# PowerMinder1sch.net
KiCad netlist of a schematic drawn in EAGLE
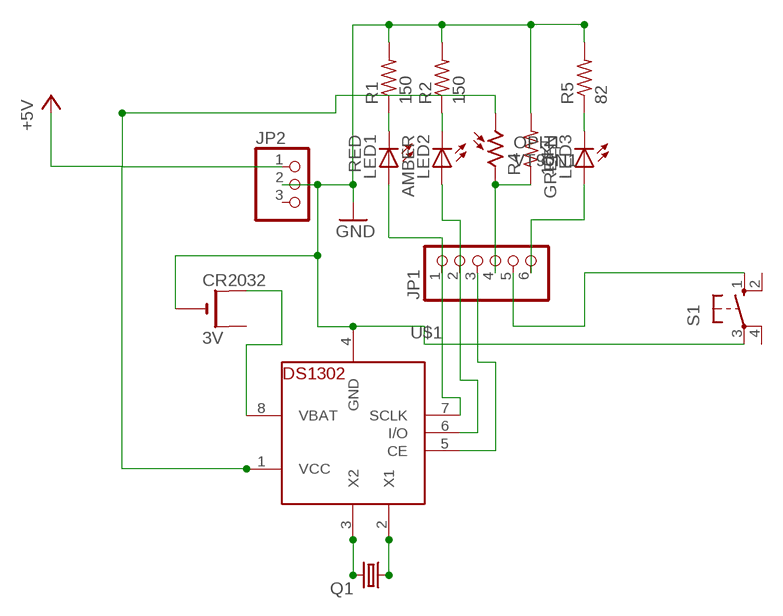
[diagram p0: schematic, sheet 1]

(export (version "E")
  (design (tool "Eeschema 10.0.6"))
  (components
    (comp (ref "CR2032")
      (value "3V")
      (footprint "eagle-import:CR2032-THRU")
      (libsource (lib "eagle-import") (part "CR2032THM"))
    )
    (comp (ref "JP1")
      (value "PINHD-1X6")
      (footprint "eagle-import:1X06")
      (libsource (lib "eagle-import") (part "PINHD-1X6"))
    )
    (comp (ref "JP2")
      (value "PINHD-1X3")
      (footprint "eagle-import:1X03")
      (libsource (lib "eagle-import") (part "PINHD-1X3"))
    )
    (comp (ref "LED1")
      (value "RED")
      (footprint "eagle-import:LED5MM")
      (libsource (lib "eagle-import") (part "LED5MM"))
    )
    (comp (ref "LED2")
      (value "AMBER")
      (footprint "eagle-import:LED5MM")
      (libsource (lib "eagle-import") (part "LED5MM"))
    )
    (comp (ref "LED3")
      (value "GREEN")
      (footprint "eagle-import:LED5MM")
      (libsource (lib "eagle-import") (part "LED5MM"))
    )
    (comp (ref "OPH1")
      (value "VT90N1")
      (footprint "eagle-import:VT900")
      (libsource (lib "eagle-import") (part "VT90N1"))
    )
    (comp (ref "Q1")
      (value "CRYSTALTC26H")
      (footprint "eagle-import:TC26H")
      (libsource (lib "eagle-import") (part "CRYSTALTC26H"))
    )
    (comp (ref "R1")
      (value "150")
      (footprint "eagle-import:0207_12")
      (libsource (lib "eagle-import") (part "R-US_0207/12"))
    )
    (comp (ref "R2")
      (value "150")
      (footprint "eagle-import:0207_12")
      (libsource (lib "eagle-import") (part "R-US_0207/12"))
    )
    (comp (ref "R4")
      (value "10K")
      (footprint "eagle-import:0207_12")
      (libsource (lib "eagle-import") (part "R-US_0207/12"))
    )
    (comp (ref "R5")
      (value "82")
      (footprint "eagle-import:0207_12")
      (libsource (lib "eagle-import") (part "R-US_0207/12"))
    )
    (comp (ref "S1")
      (value "10-XX")
      (footprint "eagle-import:B3F-10XX")
      (fields (field (name "MPN") "B3F-1000"))
      (libsource (lib "eagle-import") (part "10-XX"))
    )
    (comp (ref "U$1")
      (value "DS1302")
      (footprint "eagle-import:DIL08-ROUND")
      (libsource (lib "eagle-import") (part "DS1302"))
    )
  )
  (nets
    (net (code "1") (name "+5V") (class "Default")
      (node (ref "JP2") (pin "1") (pinfunction "1_1") (pintype "passive"))
      (node (ref "OPH1") (pin "1") (pinfunction "1_1") (pintype "passive"))
      (node (ref "U$1") (pin "1") (pinfunction "VCC_1") (pintype "power_in"))
    )
    (net (code "2") (name "GND") (class "Default")
      (node (ref "CR2032") (pin "-") (pinfunction "-_-") (pintype "passive"))
      (node (ref "JP2") (pin "2") (pinfunction "2_2") (pintype "passive"))
      (node (ref "R1") (pin "2") (pinfunction "2_2") (pintype "passive"))
      (node (ref "R2") (pin "2") (pinfunction "2_2") (pintype "passive"))
      (node (ref "R4") (pin "2") (pinfunction "2_2") (pintype "passive"))
      (node (ref "R5") (pin "2") (pinfunction "2_2") (pintype "passive"))
      (node (ref "S1") (pin "3") (pinfunction "P_3") (pintype "passive"))
      (node (ref "U$1") (pin "4") (pinfunction "GND_4") (pintype "power_in"))
    )
    (net (code "3") (name "Net-(CR2032-+)") (class "Default")
      (node (ref "CR2032") (pin "+1") (pinfunction "+_+1") (pintype "passive"))
      (node (ref "U$1") (pin "8") (pinfunction "VBAT_8") (pintype "power_in"))
    )
    (net (code "4") (name "Net-(JP1-Pad4)") (class "Default")
      (node (ref "JP1") (pin "4") (pinfunction "4_4") (pintype "passive"))
      (node (ref "OPH1") (pin "2") (pinfunction "2_2") (pintype "passive"))
      (node (ref "R4") (pin "1") (pinfunction "1_1") (pintype "passive"))
    )
    (net (code "5") (name "Net-(JP1-Pad6)") (class "Default")
      (node (ref "JP1") (pin "6") (pinfunction "6_6") (pintype "passive"))
      (node (ref "LED3") (pin "A") (pinfunction "A_A") (pintype "passive"))
    )
    (net (code "6") (name "Net-(LED1-C)") (class "Default")
      (node (ref "LED1") (pin "K") (pinfunction "C_K") (pintype "passive"))
      (node (ref "R1") (pin "1") (pinfunction "1_1") (pintype "passive"))
    )
    (net (code "7") (name "Net-(LED2-C)") (class "Default")
      (node (ref "LED2") (pin "K") (pinfunction "C_K") (pintype "passive"))
      (node (ref "R2") (pin "1") (pinfunction "1_1") (pintype "passive"))
    )
    (net (code "8") (name "Net-(LED3-C)") (class "Default")
      (node (ref "LED3") (pin "K") (pinfunction "C_K") (pintype "passive"))
      (node (ref "R5") (pin "1") (pinfunction "1_1") (pintype "passive"))
    )
    (net (code "9") (name "Net-(S1-S)") (class "Default")
      (node (ref "JP1") (pin "5") (pinfunction "5_5") (pintype "passive"))
      (node (ref "S1") (pin "1") (pinfunction "S_1") (pintype "passive"))
    )
    (net (code "10") (name "Net-(U$1-CE)") (class "Default")
      (node (ref "JP1") (pin "3") (pinfunction "3_3") (pintype "passive"))
      (node (ref "U$1") (pin "5") (pinfunction "CE_5") (pintype "input"))
    )
    (net (code "11") (name "Net-(U$1-I{slash}O)") (class "Default")
      (node (ref "JP1") (pin "2") (pinfunction "2_2") (pintype "passive"))
      (node (ref "LED2") (pin "A") (pinfunction "A_A") (pintype "passive"))
      (node (ref "U$1") (pin "6") (pinfunction "I/O_6") (pintype "bidirectional"))
    )
    (net (code "12") (name "Net-(U$1-SCLK)") (class "Default")
      (node (ref "JP1") (pin "1") (pinfunction "1_1") (pintype "passive"))
      (node (ref "LED1") (pin "A") (pinfunction "A_A") (pintype "passive"))
      (node (ref "U$1") (pin "7") (pinfunction "SCLK_7") (pintype "input"))
    )
    (net (code "13") (name "Net-(U$1-X1)") (class "Default")
      (node (ref "Q1") (pin "1") (pinfunction "1_1") (pintype "passive"))
      (node (ref "U$1") (pin "2") (pinfunction "X1_2") (pintype "passive"))
    )
    (net (code "14") (name "Net-(U$1-X2)") (class "Default")
      (node (ref "Q1") (pin "2") (pinfunction "2_2") (pintype "passive"))
      (node (ref "U$1") (pin "3") (pinfunction "X2_3") (pintype "passive"))
    )
    (net (code "15") (name "unconnected-(CR2032-+1-Pad+2)") (class "Default")
      (node (ref "CR2032") (pin "+2") (pinfunction "+1_+2") (pintype "passive"))
    )
    (net (code "16") (name "unconnected-(JP2-Pad3)") (class "Default")
      (node (ref "JP2") (pin "3") (pinfunction "3_3") (pintype "passive"))
    )
    (net (code "17") (name "unconnected-(S1-P1-Pad4)") (class "Default")
      (node (ref "S1") (pin "4") (pinfunction "P1_4") (pintype "passive"))
    )
    (net (code "18") (name "unconnected-(S1-S1-Pad2)") (class "Default")
      (node (ref "S1") (pin "2") (pinfunction "S1_2") (pintype "passive"))
    )
  )
)
